# sensor_dsp.net
KiCad netlist of a schematic drawn in EAGLE
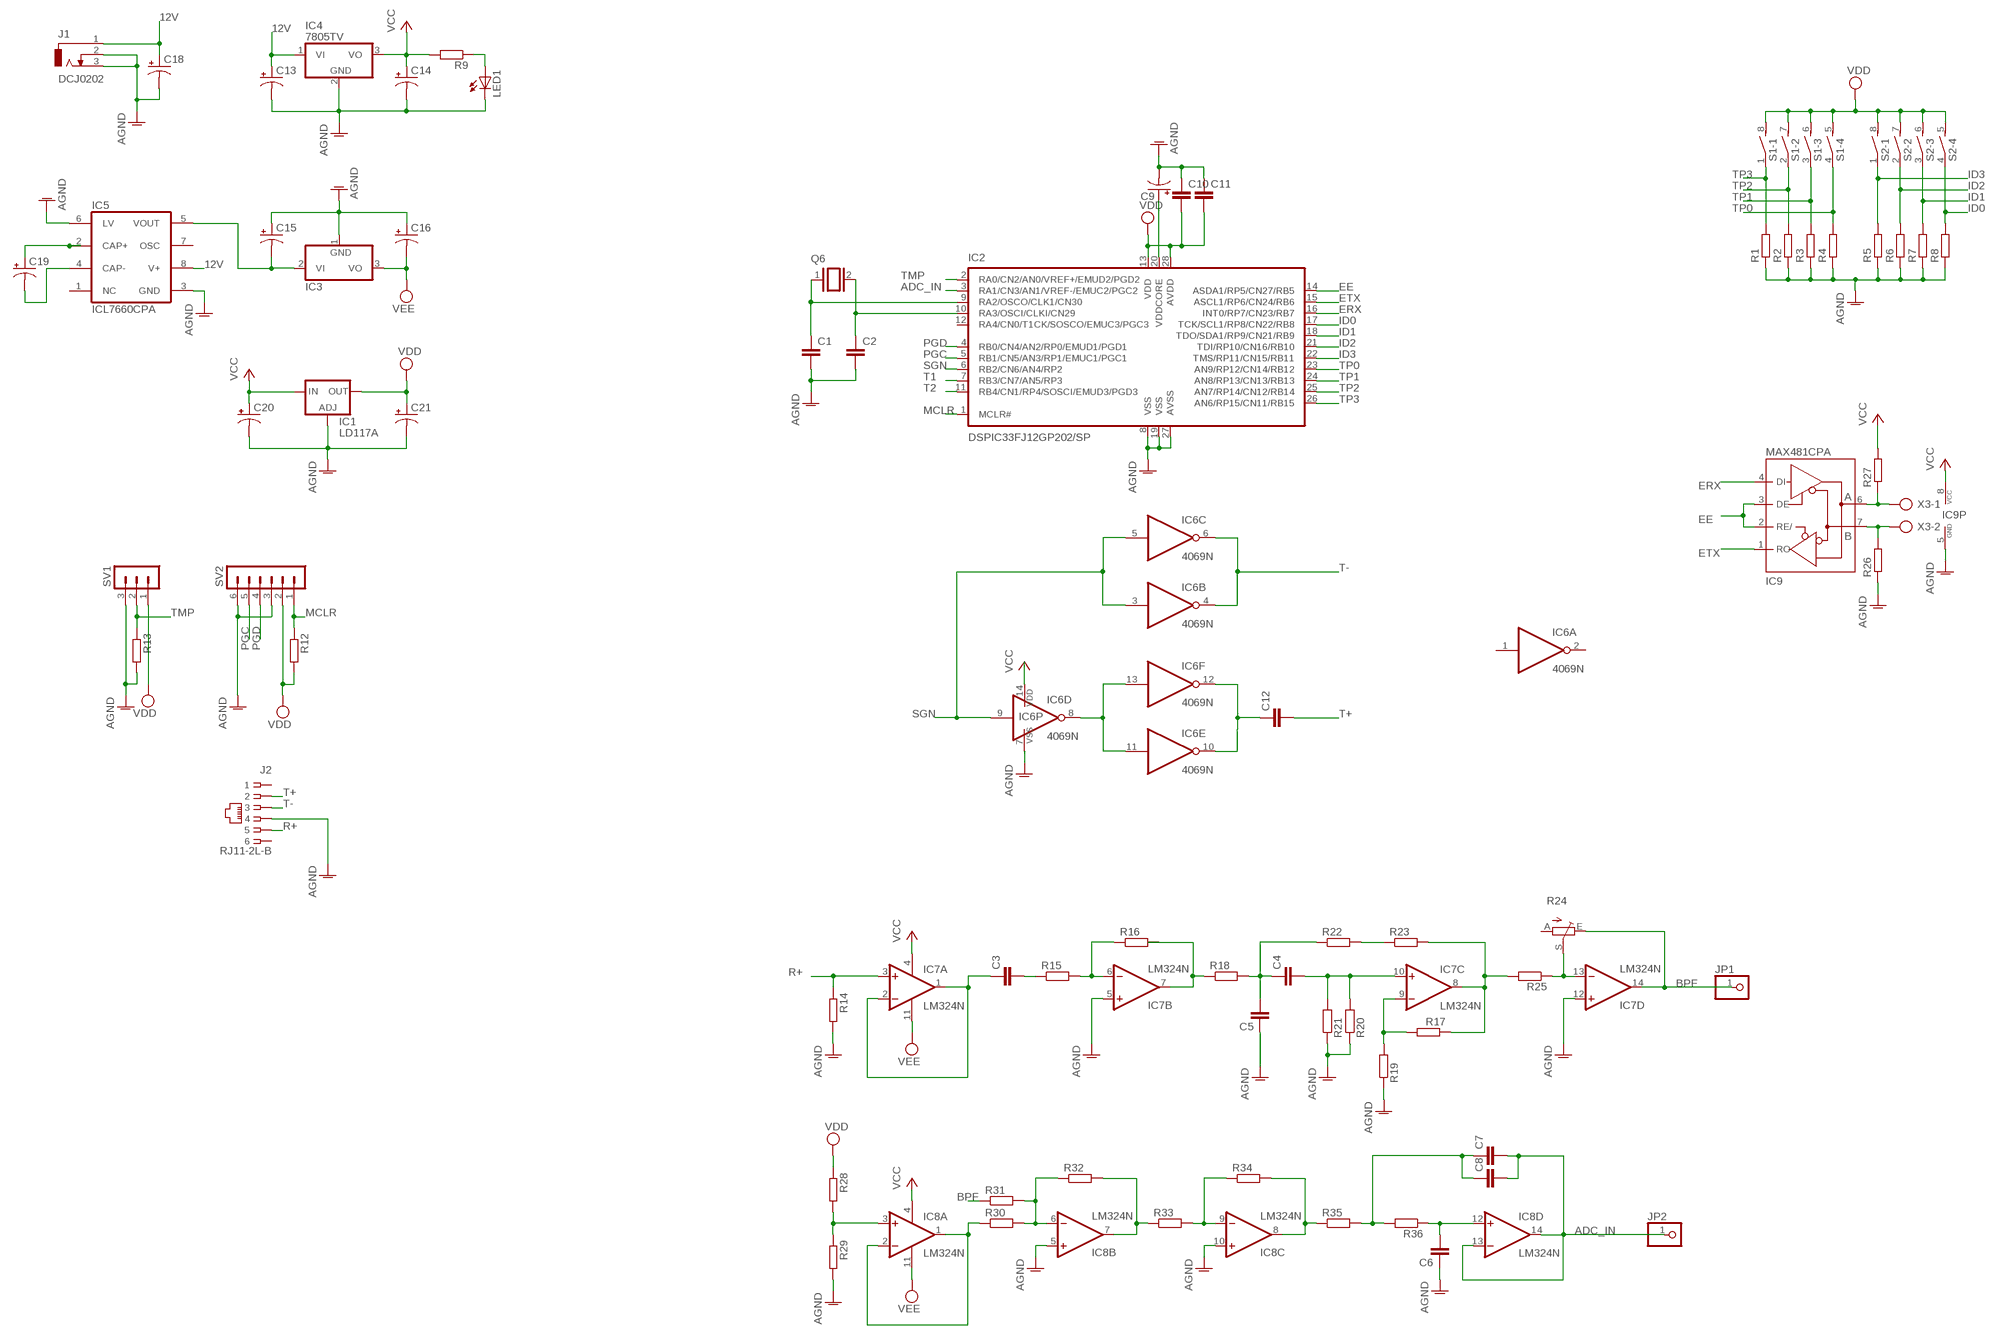
[diagram p0: schematic, sheet 1]

(export (version "E")
  (design (tool "Eeschema 10.0.6"))
  (components
    (comp (ref "C1")
      (value "C2.5/2")
      (footprint "eagle-import:C2.5-2")
      (libsource (lib "eagle-import") (part "C2.5/2"))
    )
    (comp (ref "C2")
      (value "C2.5/2")
      (footprint "eagle-import:C2.5-2")
      (libsource (lib "eagle-import") (part "C2.5/2"))
    )
    (comp (ref "C3")
      (value "C2.5/2")
      (footprint "eagle-import:C2.5-2")
      (libsource (lib "eagle-import") (part "C2.5/2"))
    )
    (comp (ref "C4")
      (value "C2.5/2")
      (footprint "eagle-import:C2.5-2")
      (libsource (lib "eagle-import") (part "C2.5/2"))
    )
    (comp (ref "C5")
      (value "C-EU050-024X044")
      (footprint "eagle-import:C050-024X044")
      (libsource (lib "eagle-import") (part "C-EU050-024X044"))
    )
    (comp (ref "C6")
      (value "C-EU050-024X044")
      (footprint "eagle-import:C050-024X044")
      (libsource (lib "eagle-import") (part "C-EU050-024X044"))
    )
    (comp (ref "C7")
      (value "C2.5/2")
      (footprint "eagle-import:C2.5-2")
      (libsource (lib "eagle-import") (part "C2.5/2"))
    )
    (comp (ref "C8")
      (value "C2.5/2")
      (footprint "eagle-import:C2.5-2")
      (libsource (lib "eagle-import") (part "C2.5/2"))
    )
    (comp (ref "C9")
      (value "CPOL-USE3.5-8")
      (footprint "eagle-import:E3,5-8")
      (libsource (lib "eagle-import") (part "CPOL-USE3.5-8"))
    )
    (comp (ref "C10")
      (value "C2.5/2")
      (footprint "eagle-import:C2.5-2")
      (libsource (lib "eagle-import") (part "C2.5/2"))
    )
    (comp (ref "C11")
      (value "C2.5/2")
      (footprint "eagle-import:C2.5-2")
      (libsource (lib "eagle-import") (part "C2.5/2"))
    )
    (comp (ref "C12")
      (value "C-EU050-024X044")
      (footprint "eagle-import:C050-024X044")
      (libsource (lib "eagle-import") (part "C-EU050-024X044"))
    )
    (comp (ref "C13")
      (value "CPOL-USE3.5-8")
      (footprint "eagle-import:E3,5-8")
      (libsource (lib "eagle-import") (part "CPOL-USE3.5-8"))
    )
    (comp (ref "C14")
      (value "CPOL-USE3.5-8")
      (footprint "eagle-import:E3,5-8")
      (libsource (lib "eagle-import") (part "CPOL-USE3.5-8"))
    )
    (comp (ref "C15")
      (value "CPOL-USE3.5-8")
      (footprint "eagle-import:E3,5-8")
      (libsource (lib "eagle-import") (part "CPOL-USE3.5-8"))
    )
    (comp (ref "C16")
      (value "CPOL-USE3.5-8")
      (footprint "eagle-import:E3,5-8")
      (libsource (lib "eagle-import") (part "CPOL-USE3.5-8"))
    )
    (comp (ref "C18")
      (value "CPOL-USE3.5-8")
      (footprint "eagle-import:E3,5-8")
      (libsource (lib "eagle-import") (part "CPOL-USE3.5-8"))
    )
    (comp (ref "C19")
      (value "CPOL-USE3.5-8")
      (footprint "eagle-import:E3,5-8")
      (libsource (lib "eagle-import") (part "CPOL-USE3.5-8"))
    )
    (comp (ref "C20")
      (value "CPOL-USE3.5-8")
      (footprint "eagle-import:E3,5-8")
      (libsource (lib "eagle-import") (part "CPOL-USE3.5-8"))
    )
    (comp (ref "C21")
      (value "CPOL-USE3.5-8")
      (footprint "eagle-import:E3,5-8")
      (libsource (lib "eagle-import") (part "CPOL-USE3.5-8"))
    )
    (comp (ref "IC1")
      (value "LD117A")
      (footprint "eagle-import:TO220S")
      (libsource (lib "eagle-import") (part "LD117A?"))
    )
    (comp (ref "IC2")
      (value "DSPIC33FJ12GP202/SP")
      (footprint "eagle-import:DIL28-3")
      (libsource (lib "eagle-import") (part "DSPIC33FJ12GP202/SP"))
    )
    (comp (ref "IC3")
      (value "79")
      (footprint "eagle-import:TO220V")
      (libsource (lib "eagle-import") (part "79"))
    )
    (comp (ref "IC4")
      (value "7805TV")
      (footprint "eagle-import:TO220V")
      (libsource (lib "eagle-import") (part "78TV05"))
    )
    (comp (ref "IC5")
      (value "ICL7660CPA")
      (footprint "eagle-import:DIL08")
      (fields (field (name "MF") "INTERSIL"))
      (libsource (lib "eagle-import") (part "ICL7660CPA"))
    )
    (comp (ref "IC6")
      (value "4069N")
      (footprint "eagle-import:DIL14")
      (libsource (lib "eagle-import") (part "4069N"))
    )
    (comp (ref "IC7")
      (value "LM324N")
      (footprint "eagle-import:DIL14")
      (libsource (lib "eagle-import") (part "LM324N"))
    )
    (comp (ref "IC8")
      (value "LM324N")
      (footprint "eagle-import:DIL14")
      (libsource (lib "eagle-import") (part "LM324N"))
    )
    (comp (ref "IC9")
      (value "MAX481CPA")
      (footprint "eagle-import:DIL08")
      (fields (field (name "MPN") "MAX481CPA+"))
      (libsource (lib "eagle-import") (part "MAX481CPA"))
    )
    (comp (ref "J1")
      (value "DCJ0202")
      (footprint "eagle-import:DCJ0202")
      (libsource (lib "eagle-import") (part "DCJ0202"))
    )
    (comp (ref "J2")
      (value "RJ11-2L-B")
      (footprint "eagle-import:RJ11-NO_SHIELD")
      (fields (field (name "MF") "TYCO ELECTRONICS"))
      (libsource (lib "eagle-import") (part "RJ11-2L-B"))
    )
    (comp (ref "JP1")
      (value "PINHD-1X1")
      (footprint "eagle-import:1X01")
      (libsource (lib "eagle-import") (part "PINHD-1X1"))
    )
    (comp (ref "JP2")
      (value "PINHD-1X1")
      (footprint "eagle-import:1X01")
      (libsource (lib "eagle-import") (part "PINHD-1X1"))
    )
    (comp (ref "LED1")
      (value "LED3MM")
      (footprint "eagle-import:LED3MM")
      (libsource (lib "eagle-import") (part "LED3MM"))
    )
    (comp (ref "Q6")
      (value "XTAL/S")
      (footprint "eagle-import:QS")
      (libsource (lib "eagle-import") (part "XTAL/S"))
    )
    (comp (ref "R1")
      (value "R-EU_0204/5")
      (footprint "eagle-import:0204_5")
      (libsource (lib "eagle-import") (part "R-EU_0204/5"))
    )
    (comp (ref "R2")
      (value "R-EU_0204/5")
      (footprint "eagle-import:0204_5")
      (libsource (lib "eagle-import") (part "R-EU_0204/5"))
    )
    (comp (ref "R3")
      (value "R-EU_0204/5")
      (footprint "eagle-import:0204_5")
      (libsource (lib "eagle-import") (part "R-EU_0204/5"))
    )
    (comp (ref "R4")
      (value "R-EU_0204/5")
      (footprint "eagle-import:0204_5")
      (libsource (lib "eagle-import") (part "R-EU_0204/5"))
    )
    (comp (ref "R5")
      (value "R-EU_0204/5")
      (footprint "eagle-import:0204_5")
      (libsource (lib "eagle-import") (part "R-EU_0204/5"))
    )
    (comp (ref "R6")
      (value "R-EU_0204/5")
      (footprint "eagle-import:0204_5")
      (libsource (lib "eagle-import") (part "R-EU_0204/5"))
    )
    (comp (ref "R7")
      (value "R-EU_0204/5")
      (footprint "eagle-import:0204_5")
      (libsource (lib "eagle-import") (part "R-EU_0204/5"))
    )
    (comp (ref "R8")
      (value "R-EU_0204/5")
      (footprint "eagle-import:0204_5")
      (libsource (lib "eagle-import") (part "R-EU_0204/5"))
    )
    (comp (ref "R9")
      (value "R-EU_0204/2V")
      (footprint "eagle-import:0204V")
      (libsource (lib "eagle-import") (part "R-EU_0204/2V"))
    )
    (comp (ref "R12")
      (value "R-EU_0204/2V")
      (footprint "eagle-import:0204V")
      (libsource (lib "eagle-import") (part "R-EU_0204/2V"))
    )
    (comp (ref "R13")
      (value "R-EU_0204/2V")
      (footprint "eagle-import:0204V")
      (libsource (lib "eagle-import") (part "R-EU_0204/2V"))
    )
    (comp (ref "R14")
      (value "R-EU_0204/7")
      (footprint "eagle-import:0204_7")
      (libsource (lib "eagle-import") (part "R-EU_0204/7"))
    )
    (comp (ref "R15")
      (value "R-EU_0204/5")
      (footprint "eagle-import:0204_5")
      (libsource (lib "eagle-import") (part "R-EU_0204/5"))
    )
    (comp (ref "R16")
      (value "R-EU_0204/2V")
      (footprint "eagle-import:0204V")
      (libsource (lib "eagle-import") (part "R-EU_0204/2V"))
    )
    (comp (ref "R17")
      (value "R-EU_0204/5")
      (footprint "eagle-import:0204_5")
      (libsource (lib "eagle-import") (part "R-EU_0204/5"))
    )
    (comp (ref "R18")
      (value "R-EU_0204/7")
      (footprint "eagle-import:0204_7")
      (libsource (lib "eagle-import") (part "resistor_R-EU_0204/7"))
    )
    (comp (ref "R19")
      (value "R-EU_0204/5")
      (footprint "eagle-import:0204_5")
      (libsource (lib "eagle-import") (part "R-EU_0204/5"))
    )
    (comp (ref "R20")
      (value "R-EU_0204/5")
      (footprint "eagle-import:0204_5")
      (libsource (lib "eagle-import") (part "R-EU_0204/5"))
    )
    (comp (ref "R21")
      (value "R-EU_0204/5")
      (footprint "eagle-import:0204_5")
      (libsource (lib "eagle-import") (part "R-EU_0204/5"))
    )
    (comp (ref "R22")
      (value "R-EU_0204/5")
      (footprint "eagle-import:0204_5")
      (libsource (lib "eagle-import") (part "R-EU_0204/5"))
    )
    (comp (ref "R23")
      (value "R-EU_0204/5")
      (footprint "eagle-import:0204_5")
      (libsource (lib "eagle-import") (part "R-EU_0204/5"))
    )
    (comp (ref "R24")
      (value "TRIM_EU-B64W")
      (footprint "eagle-import:B64W")
      (libsource (lib "eagle-import") (part "TRIM_EU-B64W"))
    )
    (comp (ref "R25")
      (value "R-EU_0204/5")
      (footprint "eagle-import:0204_5")
      (libsource (lib "eagle-import") (part "R-EU_0204/5"))
    )
    (comp (ref "R26")
      (value "R-EU_0204/5")
      (footprint "eagle-import:0204_5")
      (libsource (lib "eagle-import") (part "R-EU_0204/5"))
    )
    (comp (ref "R27")
      (value "R-EU_0204/5")
      (footprint "eagle-import:0204_5")
      (libsource (lib "eagle-import") (part "R-EU_0204/5"))
    )
    (comp (ref "R28")
      (value "R-EU_0204/5")
      (footprint "eagle-import:0204_5")
      (libsource (lib "eagle-import") (part "R-EU_0204/5"))
    )
    (comp (ref "R29")
      (value "R-EU_0204/5")
      (footprint "eagle-import:0204_5")
      (libsource (lib "eagle-import") (part "R-EU_0204/5"))
    )
    (comp (ref "R30")
      (value "R-EU_0204/7")
      (footprint "eagle-import:0204_7")
      (libsource (lib "eagle-import") (part "R-EU_0204/7"))
    )
    (comp (ref "R31")
      (value "R-EU_0204/7")
      (footprint "eagle-import:0204_7")
      (libsource (lib "eagle-import") (part "R-EU_0204/7"))
    )
    (comp (ref "R32")
      (value "R-EU_0204/2V")
      (footprint "eagle-import:0204V")
      (libsource (lib "eagle-import") (part "R-EU_0204/2V"))
    )
    (comp (ref "R33")
      (value "R-EU_0204/7")
      (footprint "eagle-import:0204_7")
      (libsource (lib "eagle-import") (part "R-EU_0204/7"))
    )
    (comp (ref "R34")
      (value "R-EU_0204/2V")
      (footprint "eagle-import:0204V")
      (libsource (lib "eagle-import") (part "R-EU_0204/2V"))
    )
    (comp (ref "R35")
      (value "R-EU_0204/7")
      (footprint "eagle-import:0204_7")
      (libsource (lib "eagle-import") (part "R-EU_0204/7"))
    )
    (comp (ref "R36")
      (value "R-EU_0204/5")
      (footprint "eagle-import:0204_5")
      (libsource (lib "eagle-import") (part "R-EU_0204/5"))
    )
    (comp (ref "S1")
      (value "DIP04S")
      (footprint "eagle-import:DIP04S")
      (libsource (lib "eagle-import") (part "DIP04S"))
    )
    (comp (ref "S2")
      (value "DIP04S")
      (footprint "eagle-import:DIP04S")
      (libsource (lib "eagle-import") (part "DIP04S"))
    )
    (comp (ref "SV1")
      (value "MA03-1")
      (footprint "eagle-import:MA03-1")
      (libsource (lib "eagle-import") (part "MA03-1"))
    )
    (comp (ref "SV2")
      (value "MA06-1")
      (footprint "eagle-import:MA06-1")
      (libsource (lib "eagle-import") (part "MA06-1"))
    )
    (comp (ref "X3")
      (value "AK300/2")
      (footprint "eagle-import:AK300_2")
      (libsource (lib "eagle-import") (part "AK300/2"))
    )
  )
  (nets
    (net (code "1") (name "/12V") (class "Default")
      (node (ref "C13") (pin "+") (pinfunction "+_+") (pintype "passive"))
      (node (ref "C18") (pin "+") (pinfunction "+_+") (pintype "passive"))
      (node (ref "IC4") (pin "1") (pinfunction "VI_1") (pintype "input"))
      (node (ref "IC5") (pin "8") (pinfunction "V+_8") (pintype "power_in"))
      (node (ref "J1") (pin "1") (pinfunction "1_1") (pintype "passive"))
    )
    (net (code "2") (name "/ADC_IN") (class "Default")
      (node (ref "C7") (pin "2") (pinfunction "2_2") (pintype "passive"))
      (node (ref "C8") (pin "2") (pinfunction "2_2") (pintype "passive"))
      (node (ref "IC2") (pin "3") (pinfunction "RA1/CN3/AN1/VREF-/EMUC2/PGC2_3") (pintype "bidirectional"))
      (node (ref "IC8") (pin "13") (pinfunction "-IN_13") (pintype "input"))
      (node (ref "IC8") (pin "14") (pinfunction "OUT_14") (pintype "output"))
      (node (ref "JP2") (pin "1") (pinfunction "1_1") (pintype "passive"))
    )
    (net (code "3") (name "/BPF") (class "Default")
      (node (ref "IC7") (pin "14") (pinfunction "OUT_14") (pintype "output"))
      (node (ref "JP1") (pin "1") (pinfunction "1_1") (pintype "passive"))
      (node (ref "R24") (pin "E") (pinfunction "E_E") (pintype "passive"))
      (node (ref "R31") (pin "1") (pinfunction "1_1") (pintype "passive"))
    )
    (net (code "4") (name "/EE") (class "Default")
      (node (ref "IC2") (pin "14") (pinfunction "ASDA1/RP5/CN27/RB5_14") (pintype "bidirectional"))
      (node (ref "IC9") (pin "2") (pinfunction "RE/_2") (pintype "input"))
      (node (ref "IC9") (pin "3") (pinfunction "DE_3") (pintype "input"))
    )
    (net (code "5") (name "/ERX") (class "Default")
      (node (ref "IC2") (pin "16") (pinfunction "INT0/RP7/CN23/RB7_16") (pintype "bidirectional"))
      (node (ref "IC9") (pin "4") (pinfunction "DI_4") (pintype "input"))
    )
    (net (code "6") (name "/ETX") (class "Default")
      (node (ref "IC2") (pin "15") (pinfunction "ASCL1/RP6/CN24/RB6_15") (pintype "bidirectional"))
      (node (ref "IC9") (pin "1") (pinfunction "RO_1") (pintype "output"))
    )
    (net (code "7") (name "/ID0") (class "Default")
      (node (ref "IC2") (pin "17") (pinfunction "TCK/SCL1/RP8/CN22/RB8_17") (pintype "bidirectional"))
      (node (ref "R8") (pin "2") (pinfunction "2_2") (pintype "passive"))
      (node (ref "S2") (pin "4") (pinfunction "1_4") (pintype "passive"))
    )
    (net (code "8") (name "/ID1") (class "Default")
      (node (ref "IC2") (pin "18") (pinfunction "TDO/SDA1/RP9/CN21/RB9_18") (pintype "bidirectional"))
      (node (ref "R7") (pin "2") (pinfunction "2_2") (pintype "passive"))
      (node (ref "S2") (pin "3") (pinfunction "1_3") (pintype "passive"))
    )
    (net (code "9") (name "/ID2") (class "Default")
      (node (ref "IC2") (pin "21") (pinfunction "TDI/RP10/CN16/RB10_21") (pintype "bidirectional"))
      (node (ref "R6") (pin "2") (pinfunction "2_2") (pintype "passive"))
      (node (ref "S2") (pin "2") (pinfunction "1_2") (pintype "passive"))
    )
    (net (code "10") (name "/ID3") (class "Default")
      (node (ref "IC2") (pin "22") (pinfunction "TMS/RP11/CN15/RB11_22") (pintype "bidirectional"))
      (node (ref "R5") (pin "2") (pinfunction "2_2") (pintype "passive"))
      (node (ref "S2") (pin "1") (pinfunction "1_1") (pintype "passive"))
    )
    (net (code "11") (name "/MCLR") (class "Default")
      (node (ref "IC2") (pin "1") (pinfunction "MCLR#_1") (pintype "input"))
      (node (ref "R12") (pin "1") (pinfunction "1_1") (pintype "passive"))
      (node (ref "SV2") (pin "1") (pinfunction "1_1") (pintype "passive"))
    )
    (net (code "12") (name "/PGC") (class "Default")
      (node (ref "IC2") (pin "5") (pinfunction "RB1/CN5/AN3/RP1/EMUC1/PGC1_5") (pintype "bidirectional"))
      (node (ref "SV2") (pin "5") (pinfunction "5_5") (pintype "passive"))
    )
    (net (code "13") (name "/PGD") (class "Default")
      (node (ref "IC2") (pin "4") (pinfunction "RB0/CN4/AN2/RP0/EMUD1/PGD1_4") (pintype "bidirectional"))
      (node (ref "SV2") (pin "4") (pinfunction "4_4") (pintype "passive"))
    )
    (net (code "14") (name "/R+") (class "Default")
      (node (ref "IC7") (pin "3") (pinfunction "+IN_3") (pintype "input"))
      (node (ref "J2") (pin "5") (pinfunction "5_5") (pintype "passive"))
      (node (ref "R14") (pin "1") (pinfunction "1_1") (pintype "passive"))
    )
    (net (code "15") (name "/SGN") (class "Default")
      (node (ref "IC2") (pin "6") (pinfunction "RB2/CN6/AN4/RP2_6") (pintype "bidirectional"))
      (node (ref "IC6") (pin "3") (pinfunction "I_3") (pintype "input"))
      (node (ref "IC6") (pin "5") (pinfunction "I_5") (pintype "input"))
      (node (ref "IC6") (pin "9") (pinfunction "I_9") (pintype "input"))
    )
    (net (code "16") (name "/T+") (class "Default")
      (node (ref "C12") (pin "2") (pinfunction "2_2") (pintype "passive"))
      (node (ref "J2") (pin "2") (pinfunction "2_2") (pintype "passive"))
    )
    (net (code "17") (name "/T-") (class "Default")
      (node (ref "IC6") (pin "4") (pinfunction "O_4") (pintype "output"))
      (node (ref "IC6") (pin "6") (pinfunction "O_6") (pintype "output"))
      (node (ref "J2") (pin "3") (pinfunction "3_3") (pintype "passive"))
    )
    (net (code "18") (name "/T1") (class "Default")
      (node (ref "IC2") (pin "7") (pinfunction "RB3/CN7/AN5/RP3_7") (pintype "bidirectional"))
    )
    (net (code "19") (name "/T2") (class "Default")
      (node (ref "IC2") (pin "11") (pinfunction "RB4/CN1/RP4/SOSCI/EMUD3/PGD3_11") (pintype "bidirectional"))
    )
    (net (code "20") (name "/TMP") (class "Default")
      (node (ref "IC2") (pin "2") (pinfunction "RA0/CN2/AN0/VREF+/EMUD2/PGD2_2") (pintype "bidirectional"))
      (node (ref "R13") (pin "1") (pinfunction "1_1") (pintype "passive"))
      (node (ref "SV1") (pin "2") (pinfunction "2_2") (pintype "passive"))
    )
    (net (code "21") (name "/TP0") (class "Default")
      (node (ref "IC2") (pin "23") (pinfunction "AN9/RP12/CN14/RB12_23") (pintype "bidirectional"))
      (node (ref "R4") (pin "2") (pinfunction "2_2") (pintype "passive"))
      (node (ref "S1") (pin "4") (pinfunction "1_4") (pintype "passive"))
    )
    (net (code "22") (name "/TP1") (class "Default")
      (node (ref "IC2") (pin "24") (pinfunction "AN8/RP13/CN13/RB13_24") (pintype "bidirectional"))
      (node (ref "R3") (pin "2") (pinfunction "2_2") (pintype "passive"))
      (node (ref "S1") (pin "3") (pinfunction "1_3") (pintype "passive"))
    )
    (net (code "23") (name "/TP2") (class "Default")
      (node (ref "IC2") (pin "25") (pinfunction "AN7/RP14/CN12/RB14_25") (pintype "bidirectional"))
      (node (ref "R2") (pin "2") (pinfunction "2_2") (pintype "passive"))
      (node (ref "S1") (pin "2") (pinfunction "1_2") (pintype "passive"))
    )
    (net (code "24") (name "/TP3") (class "Default")
      (node (ref "IC2") (pin "26") (pinfunction "AN6/RP15/CN11/RB15_26") (pintype "bidirectional"))
      (node (ref "R1") (pin "2") (pinfunction "2_2") (pintype "passive"))
      (node (ref "S1") (pin "1") (pinfunction "1_1") (pintype "passive"))
    )
    (net (code "25") (name "AGND") (class "Default")
      (node (ref "C1") (pin "2") (pinfunction "2_2") (pintype "passive"))
      (node (ref "C10") (pin "1") (pinfunction "1_1") (pintype "passive"))
      (node (ref "C11") (pin "1") (pinfunction "1_1") (pintype "passive"))
      (node (ref "C13") (pin "-") (pinfunction "-_-") (pintype "passive"))
      (node (ref "C14") (pin "-") (pinfunction "-_-") (pintype "passive"))
      (node (ref "C15") (pin "+") (pinfunction "+_+") (pintype "passive"))
      (node (ref "C16") (pin "+") (pinfunction "+_+") (pintype "passive"))
      (node (ref "C18") (pin "-") (pinfunction "-_-") (pintype "passive"))
      (node (ref "C2") (pin "2") (pinfunction "2_2") (pintype "passive"))
      (node (ref "C20") (pin "-") (pinfunction "-_-") (pintype "passive"))
      (node (ref "C21") (pin "-") (pinfunction "-_-") (pintype "passive"))
      (node (ref "C5") (pin "1") (pinfunction "1_1") (pintype "passive"))
      (node (ref "C6") (pin "1") (pinfunction "1_1") (pintype "passive"))
      (node (ref "C9") (pin "-") (pinfunction "-_-") (pintype "passive"))
      (node (ref "IC1") (pin "1") (pinfunction "ADJ_1") (pintype "input"))
      (node (ref "IC2") (pin "19") (pinfunction "VSS_19") (pintype "power_in"))
      (node (ref "IC2") (pin "27") (pinfunction "AVSS_27") (pintype "power_in"))
      (node (ref "IC2") (pin "8") (pinfunction "VSS_8") (pintype "power_in"))
      (node (ref "IC3") (pin "1") (pinfunction "GND_1") (pintype "passive"))
      (node (ref "IC4") (pin "2") (pinfunction "GND_2") (pintype "passive"))
      (node (ref "IC5") (pin "3") (pinfunction "GND_3") (pintype "power_in"))
      (node (ref "IC5") (pin "6") (pinfunction "LV_6") (pintype "passive"))
      (node (ref "IC6") (pin "7") (pinfunction "VSS_7") (pintype "power_in"))
      (node (ref "IC7") (pin "12") (pinfunction "+IN_12") (pintype "input"))
      (node (ref "IC7") (pin "5") (pinfunction "+IN_5") (pintype "input"))
      (node (ref "IC8") (pin "10") (pinfunction "+IN_10") (pintype "input"))
      (node (ref "IC8") (pin "5") (pinfunction "+IN_5") (pintype "input"))
      (node (ref "IC9") (pin "5") (pinfunction "GND_5") (pintype "power_in"))
      (node (ref "J1") (pin "2") (pinfunction "2_2") (pintype "passive"))
      (node (ref "J1") (pin "3") (pinfunction "3_3") (pintype "passive"))
      (node (ref "J2") (pin "4") (pinfunction "4_4") (pintype "passive"))
      (node (ref "LED1") (pin "K") (pinfunction "C_K") (pintype "passive"))
      (node (ref "R1") (pin "1") (pinfunction "1_1") (pintype "passive"))
      (node (ref "R13") (pin "2") (pinfunction "2_2") (pintype "passive"))
      (node (ref "R14") (pin "2") (pinfunction "2_2") (pintype "passive"))
      (node (ref "R19") (pin "1") (pinfunction "1_1") (pintype "passive"))
      (node (ref "R2") (pin "1") (pinfunction "1_1") (pintype "passive"))
      (node (ref "R20") (pin "1") (pinfunction "1_1") (pintype "passive"))
      (node (ref "R21") (pin "1") (pinfunction "1_1") (pintype "passive"))
      (node (ref "R26") (pin "1") (pinfunction "1_1") (pintype "passive"))
      (node (ref "R29") (pin "2") (pinfunction "2_2") (pintype "passive"))
      (node (ref "R3") (pin "1") (pinfunction "1_1") (pintype "passive"))
      (node (ref "R4") (pin "1") (pinfunction "1_1") (pintype "passive"))
      (node (ref "R5") (pin "1") (pinfunction "1_1") (pintype "passive"))
      (node (ref "R6") (pin "1") (pinfunction "1_1") (pintype "passive"))
      (node (ref "R7") (pin "1") (pinfunction "1_1") (pintype "passive"))
      (node (ref "R8") (pin "1") (pinfunction "1_1") (pintype "passive"))
      (node (ref "SV1") (pin "3") (pinfunction "3_3") (pintype "passive"))
      (node (ref "SV2") (pin "3") (pinfunction "3_3") (pintype "passive"))
      (node (ref "SV2") (pin "6") (pinfunction "6_6") (pintype "passive"))
    )
    (net (code "26") (name "Net-(C3-Pad2)") (class "Default")
      (node (ref "C3") (pin "2") (pinfunction "2_2") (pintype "passive"))
      (node (ref "R15") (pin "1") (pinfunction "1_1") (pintype "passive"))
    )
    (net (code "27") (name "Net-(C4-Pad1)") (class "Default")
      (node (ref "C4") (pin "1") (pinfunction "1_1") (pintype "passive"))
      (node (ref "C5") (pin "2") (pinfunction "2_2") (pintype "passive"))
      (node (ref "R18") (pin "2") (pinfunction "2_2") (pintype "passive"))
      (node (ref "R22") (pin "1") (pinfunction "1_1") (pintype "passive"))
    )
    (net (code "28") (name "Net-(C7-Pad1)") (class "Default")
      (node (ref "C7") (pin "1") (pinfunction "1_1") (pintype "passive"))
      (node (ref "C8") (pin "1") (pinfunction "1_1") (pintype "passive"))
      (node (ref "R35") (pin "2") (pinfunction "2_2") (pintype "passive"))
      (node (ref "R36") (pin "2") (pinfunction "2_2") (pintype "passive"))
    )
    (net (code "29") (name "Net-(IC2-RA2{slash}OSCO{slash}CLK1{slash}CN30)") (class "Default")
      (node (ref "C1") (pin "1") (pinfunction "1_1") (pintype "passive"))
      (node (ref "IC2") (pin "9") (pinfunction "RA2/OSCO/CLK1/CN30_9") (pintype "bidirectional"))
      (node (ref "Q6") (pin "1") (pinfunction "1_1") (pintype "passive"))
    )
    (net (code "30") (name "Net-(IC2-RA3{slash}OSCI{slash}CLKI{slash}CN29)") (class "Default")
      (node (ref "C2") (pin "1") (pinfunction "1_1") (pintype "passive"))
      (node (ref "IC2") (pin "10") (pinfunction "RA3/OSCI/CLKI/CN29_10") (pintype "bidirectional"))
      (node (ref "Q6") (pin "2") (pinfunction "2_2") (pintype "passive"))
    )
    (net (code "31") (name "Net-(IC2-VDDCORE)") (class "Default")
      (node (ref "C9") (pin "+") (pinfunction "+_+") (pintype "passive"))
      (node (ref "IC2") (pin "20") (pinfunction "VDDCORE_20") (pintype "power_in"))
    )
    (net (code "32") (name "Net-(IC3-VI)") (class "Default")
      (node (ref "C15") (pin "-") (pinfunction "-_-") (pintype "passive"))
      (node (ref "IC3") (pin "2") (pinfunction "VI_2") (pintype "input"))
      (node (ref "IC5") (pin "5") (pinfunction "VOUT_5") (pintype "output"))
    )
    (net (code "33") (name "Net-(IC5-CAP+)") (class "Default")
      (node (ref "C19") (pin "+") (pinfunction "+_+") (pintype "passive"))
      (node (ref "IC5") (pin "2") (pinfunction "CAP+_2") (pintype "passive"))
    )
    (net (code "34") (name "Net-(IC5-CAP-)") (class "Default")
      (node (ref "C19") (pin "-") (pinfunction "-_-") (pintype "passive"))
      (node (ref "IC5") (pin "4") (pinfunction "CAP-_4") (pintype "passive"))
    )
    (net (code "35") (name "Net-(IC6D-O)") (class "Default")
      (node (ref "IC6") (pin "11") (pinfunction "I_11") (pintype "input"))
      (node (ref "IC6") (pin "13") (pinfunction "I_13") (pintype "input"))
      (node (ref "IC6") (pin "8") (pinfunction "O_8") (pintype "output"))
    )
    (net (code "36") (name "Net-(IC6E-O)") (class "Default")
      (node (ref "C12") (pin "1") (pinfunction "1_1") (pintype "passive"))
      (node (ref "IC6") (pin "10") (pinfunction "O_10") (pintype "output"))
      (node (ref "IC6") (pin "12") (pinfunction "O_12") (pintype "output"))
    )
    (net (code "37") (name "Net-(IC7A--IN)") (class "Default")
      (node (ref "C3") (pin "1") (pinfunction "1_1") (pintype "passive"))
      (node (ref "IC7") (pin "1") (pinfunction "OUT_1") (pintype "output"))
      (node (ref "IC7") (pin "2") (pinfunction "-IN_2") (pintype "input"))
    )
    (net (code "38") (name "Net-(IC7B--IN)") (class "Default")
      (node (ref "IC7") (pin "6") (pinfunction "-IN_6") (pintype "input"))
      (node (ref "R15") (pin "2") (pinfunction "2_2") (pintype "passive"))
      (node (ref "R16") (pin "1") (pinfunction "1_1") (pintype "passive"))
    )
    (net (code "39") (name "Net-(IC7B-OUT)") (class "Default")
      (node (ref "IC7") (pin "7") (pinfunction "OUT_7") (pintype "output"))
      (node (ref "R16") (pin "2") (pinfunction "2_2") (pintype "passive"))
      (node (ref "R18") (pin "1") (pinfunction "1_1") (pintype "passive"))
    )
    (net (code "40") (name "Net-(IC7C-+IN)") (class "Default")
      (node (ref "C4") (pin "2") (pinfunction "2_2") (pintype "passive"))
      (node (ref "IC7") (pin "10") (pinfunction "+IN_10") (pintype "input"))
      (node (ref "R20") (pin "2") (pinfunction "2_2") (pintype "passive"))
      (node (ref "R21") (pin "2") (pinfunction "2_2") (pintype "passive"))
    )
    (net (code "41") (name "Net-(IC7C--IN)") (class "Default")
      (node (ref "IC7") (pin "9") (pinfunction "-IN_9") (pintype "input"))
      (node (ref "R17") (pin "2") (pinfunction "2_2") (pintype "passive"))
      (node (ref "R19") (pin "2") (pinfunction "2_2") (pintype "passive"))
    )
    (net (code "42") (name "Net-(IC7C-OUT)") (class "Default")
      (node (ref "IC7") (pin "8") (pinfunction "OUT_8") (pintype "output"))
      (node (ref "R17") (pin "1") (pinfunction "1_1") (pintype "passive"))
      (node (ref "R23") (pin "2") (pinfunction "2_2") (pintype "passive"))
      (node (ref "R25") (pin "2") (pinfunction "2_2") (pintype "passive"))
    )
    (net (code "43") (name "Net-(IC7D--IN)") (class "Default")
      (node (ref "IC7") (pin "13") (pinfunction "-IN_13") (pintype "input"))
      (node (ref "R24") (pin "S") (pinfunction "S_S") (pintype "passive"))
      (node (ref "R25") (pin "1") (pinfunction "1_1") (pintype "passive"))
    )
    (net (code "44") (name "Net-(IC8A-+IN)") (class "Default")
      (node (ref "IC8") (pin "3") (pinfunction "+IN_3") (pintype "input"))
      (node (ref "R28") (pin "2") (pinfunction "2_2") (pintype "passive"))
      (node (ref "R29") (pin "1") (pinfunction "1_1") (pintype "passive"))
    )
    (net (code "45") (name "Net-(IC8A--IN)") (class "Default")
      (node (ref "IC8") (pin "1") (pinfunction "OUT_1") (pintype "output"))
      (node (ref "IC8") (pin "2") (pinfunction "-IN_2") (pintype "input"))
      (node (ref "R30") (pin "1") (pinfunction "1_1") (pintype "passive"))
    )
    (net (code "46") (name "Net-(IC8B--IN)") (class "Default")
      (node (ref "IC8") (pin "6") (pinfunction "-IN_6") (pintype "input"))
      (node (ref "R30") (pin "2") (pinfunction "2_2") (pintype "passive"))
      (node (ref "R31") (pin "2") (pinfunction "2_2") (pintype "passive"))
      (node (ref "R32") (pin "1") (pinfunction "1_1") (pintype "passive"))
    )
    (net (code "47") (name "Net-(IC8B-OUT)") (class "Default")
      (node (ref "IC8") (pin "7") (pinfunction "OUT_7") (pintype "output"))
      (node (ref "R32") (pin "2") (pinfunction "2_2") (pintype "passive"))
      (node (ref "R33") (pin "1") (pinfunction "1_1") (pintype "passive"))
    )
    (net (code "48") (name "Net-(IC8C--IN)") (class "Default")
      (node (ref "IC8") (pin "9") (pinfunction "-IN_9") (pintype "input"))
      (node (ref "R33") (pin "2") (pinfunction "2_2") (pintype "passive"))
      (node (ref "R34") (pin "1") (pinfunction "1_1") (pintype "passive"))
    )
    (net (code "49") (name "Net-(IC8C-OUT)") (class "Default")
      (node (ref "IC8") (pin "8") (pinfunction "OUT_8") (pintype "output"))
      (node (ref "R34") (pin "2") (pinfunction "2_2") (pintype "passive"))
      (node (ref "R35") (pin "1") (pinfunction "1_1") (pintype "passive"))
    )
    (net (code "50") (name "Net-(IC8D-+IN)") (class "Default")
      (node (ref "C6") (pin "2") (pinfunction "2_2") (pintype "passive"))
      (node (ref "IC8") (pin "12") (pinfunction "+IN_12") (pintype "input"))
      (node (ref "R36") (pin "1") (pinfunction "1_1") (pintype "passive"))
    )
    (net (code "51") (name "Net-(IC9A-A)") (class "Default")
      (node (ref "IC9") (pin "6") (pinfunction "A_6") (pintype "passive"))
      (node (ref "R27") (pin "1") (pinfunction "1_1") (pintype "passive"))
      (node (ref "X3") (pin "1") (pinfunction "KL_1") (pintype "passive"))
    )
    (net (code "52") (name "Net-(IC9A-B)") (class "Default")
      (node (ref "IC9") (pin "7") (pinfunction "B_7") (pintype "passive"))
      (node (ref "R26") (pin "2") (pinfunction "2_2") (pintype "passive"))
      (node (ref "X3") (pin "2") (pinfunction "KL_2") (pintype "passive"))
    )
    (net (code "53") (name "Net-(LED1-PadA)") (class "Default")
      (node (ref "LED1") (pin "A") (pinfunction "A_A") (pintype "passive"))
      (node (ref "R9") (pin "1") (pinfunction "1_1") (pintype "passive"))
    )
    (net (code "54") (name "Net-(R22-Pad2)") (class "Default")
      (node (ref "R22") (pin "2") (pinfunction "2_2") (pintype "passive"))
      (node (ref "R23") (pin "1") (pinfunction "1_1") (pintype "passive"))
    )
    (net (code "55") (name "VCC") (class "Default")
      (node (ref "C14") (pin "+") (pinfunction "+_+") (pintype "passive"))
      (node (ref "C20") (pin "+") (pinfunction "+_+") (pintype "passive"))
      (node (ref "IC1") (pin "3") (pinfunction "IN_3") (pintype "input"))
      (node (ref "IC4") (pin "3") (pinfunction "VO_3") (pintype "passive"))
      (node (ref "IC6") (pin "14") (pinfunction "VDD_14") (pintype "power_in"))
      (node (ref "IC7") (pin "4") (pinfunction "V+_4") (pintype "power_in"))
      (node (ref "IC8") (pin "4") (pinfunction "V+_4") (pintype "power_in"))
      (node (ref "IC9") (pin "8") (pinfunction "VCC_8") (pintype "power_in"))
      (node (ref "R27") (pin "2") (pinfunction "2_2") (pintype "passive"))
      (node (ref "R9") (pin "2") (pinfunction "2_2") (pintype "passive"))
    )
    (net (code "56") (name "VDD") (class "Default")
      (node (ref "C10") (pin "2") (pinfunction "2_2") (pintype "passive"))
      (node (ref "C11") (pin "2") (pinfunction "2_2") (pintype "passive"))
      (node (ref "C21") (pin "+") (pinfunction "+_+") (pintype "passive"))
      (node (ref "IC1") (pin "2") (pinfunction "OUT_2") (pintype "passive"))
      (node (ref "IC2") (pin "13") (pinfunction "VDD_13") (pintype "power_in"))
      (node (ref "IC2") (pin "28") (pinfunction "AVDD_28") (pintype "power_in"))
      (node (ref "R12") (pin "2") (pinfunction "2_2") (pintype "passive"))
      (node (ref "R28") (pin "1") (pinfunction "1_1") (pintype "passive"))
      (node (ref "S1") (pin "5") (pinfunction "2_5") (pintype "passive"))
      (node (ref "S1") (pin "6") (pinfunction "2_6") (pintype "passive"))
      (node (ref "S1") (pin "7") (pinfunction "2_7") (pintype "passive"))
      (node (ref "S1") (pin "8") (pinfunction "2_8") (pintype "passive"))
      (node (ref "S2") (pin "5") (pinfunction "2_5") (pintype "passive"))
      (node (ref "S2") (pin "6") (pinfunction "2_6") (pintype "passive"))
      (node (ref "S2") (pin "7") (pinfunction "2_7") (pintype "passive"))
      (node (ref "S2") (pin "8") (pinfunction "2_8") (pintype "passive"))
      (node (ref "SV1") (pin "1") (pinfunction "1_1") (pintype "passive"))
      (node (ref "SV2") (pin "2") (pinfunction "2_2") (pintype "passive"))
    )
    (net (code "57") (name "VEE") (class "Default")
      (node (ref "C16") (pin "-") (pinfunction "-_-") (pintype "passive"))
      (node (ref "IC3") (pin "3") (pinfunction "VO_3") (pintype "passive"))
      (node (ref "IC7") (pin "11") (pinfunction "V-_11") (pintype "power_in"))
      (node (ref "IC8") (pin "11") (pinfunction "V-_11") (pintype "power_in"))
    )
    (net (code "58") (name "unconnected-(IC2-RA4{slash}CN0{slash}T1CK{slash}SOSCO{slash}EMUC3{slash}PGC3-Pad12)") (class "Default")
      (node (ref "IC2") (pin "12") (pinfunction "RA4/CN0/T1CK/SOSCO/EMUC3/PGC3_12") (pintype "bidirectional"))
    )
    (net (code "59") (name "unconnected-(IC5-NC-Pad1)") (class "Default")
      (node (ref "IC5") (pin "1") (pinfunction "NC_1") (pintype "no_connect"))
    )
    (net (code "60") (name "unconnected-(IC5-OSC-Pad7)") (class "Default")
      (node (ref "IC5") (pin "7") (pinfunction "OSC_7") (pintype "output"))
    )
    (net (code "61") (name "unconnected-(IC6A-I-Pad1)") (class "Default")
      (node (ref "IC6") (pin "1") (pinfunction "I_1") (pintype "input"))
    )
    (net (code "62") (name "unconnected-(IC6A-O-Pad2)") (class "Default")
      (node (ref "IC6") (pin "2") (pinfunction "O_2") (pintype "output"))
    )
    (net (code "63") (name "unconnected-(J2-Pad1)") (class "Default")
      (node (ref "J2") (pin "1") (pinfunction "1_1") (pintype "passive"))
    )
    (net (code "64") (name "unconnected-(J2-Pad6)") (class "Default")
      (node (ref "J2") (pin "6") (pinfunction "6_6") (pintype "passive"))
    )
    (net (code "65") (name "unconnected-(R24-PadA)") (class "Default")
      (node (ref "R24") (pin "A") (pinfunction "A_A") (pintype "passive"))
    )
  )
)
